# BeerTape_Hardware.net
KiCad netlist of a schematic drawn in EAGLE
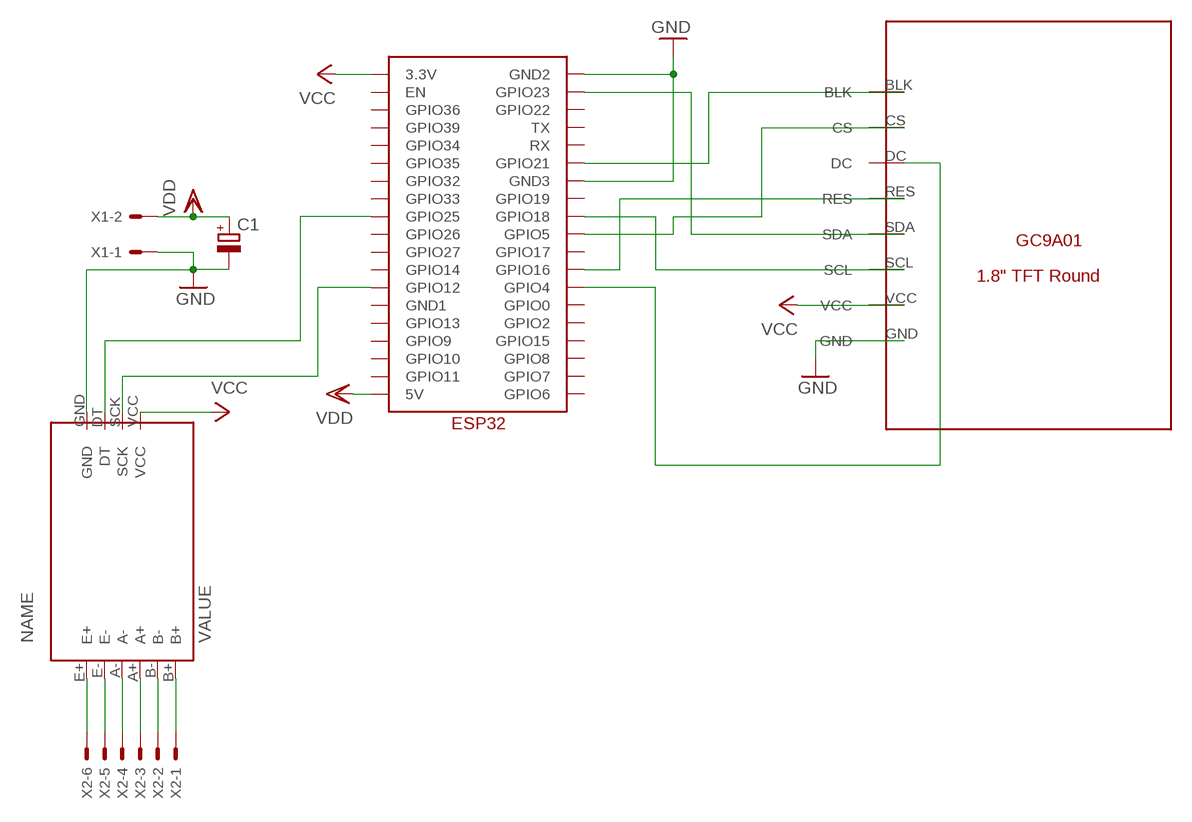
[diagram p0: schematic, sheet 1]

(export (version "E")
  (design (tool "Eeschema 10.0.6"))
  (components
    (comp (ref "C1")
      (value "CPOL-EUE2,5-6E")
      (footprint "eagle-import:E2,5-6E")
      (libsource (lib "eagle-import") (part "CPOL-EUE2,5-6E"))
    )
    (comp (ref "HX711")
      (value "HX711")
      (footprint "eagle-import:HX711")
      (libsource (lib "eagle-import") (part "HX711A"))
    )
    (comp (ref "U$1")
      (value "GC9A01")
      (footprint "eagle-import:GC9A01")
      (libsource (lib "eagle-import") (part "GC9A01"))
    )
    (comp (ref "U$2")
      (value "ESP32")
      (footprint "eagle-import:ESP32")
      (libsource (lib "eagle-import") (part "ESP32"))
    )
    (comp (ref "X1")
      (value "KK-156-2")
      (footprint "eagle-import:KK-156-2")
      (fields (field (name "MF") "MOLEX"))
      (libsource (lib "eagle-import") (part "KK-156-2"))
    )
    (comp (ref "X2")
      (value "22-23-2061")
      (footprint "eagle-import:22-23-2061")
      (fields (field (name "MF") "MOLEX"))
      (libsource (lib "eagle-import") (part "22-23-2061"))
    )
  )
  (nets
    (net (code "1") (name "GND") (class "Default")
      (node (ref "C1") (pin "-") (pinfunction "-_-") (pintype "passive"))
      (node (ref "HX711") (pin "GND") (pinfunction "GND_GND") (pintype "bidirectional"))
      (node (ref "U$1") (pin "GND") (pinfunction "GND_GND") (pintype "bidirectional"))
      (node (ref "U$2") (pin "GND2") (pinfunction "GND2_GND2") (pintype "bidirectional"))
      (node (ref "U$2") (pin "GND3") (pinfunction "GND3_GND3") (pintype "bidirectional"))
      (node (ref "X1") (pin "1") (pinfunction "S_1") (pintype "passive"))
    )
    (net (code "2") (name "Net-(HX711-PadDT)") (class "Default")
      (node (ref "HX711") (pin "DT") (pinfunction "DT_DT") (pintype "bidirectional"))
      (node (ref "U$2") (pin "GPIO25") (pinfunction "GPIO25_GPIO25") (pintype "bidirectional"))
    )
    (net (code "3") (name "Net-(HX711-PadSCK)") (class "Default")
      (node (ref "HX711") (pin "SCK") (pinfunction "SCK_SCK") (pintype "bidirectional"))
      (node (ref "U$2") (pin "GPIO12") (pinfunction "GPIO12_GPIO12") (pintype "bidirectional"))
    )
    (net (code "4") (name "Net-(U$1-PadBLK)") (class "Default")
      (node (ref "U$1") (pin "BLK") (pinfunction "BLK_BLK") (pintype "bidirectional"))
      (node (ref "U$2") (pin "GPIO21") (pinfunction "GPIO21_GPIO21") (pintype "bidirectional"))
    )
    (net (code "5") (name "Net-(U$1-PadCS)") (class "Default")
      (node (ref "U$1") (pin "CS") (pinfunction "CS_CS") (pintype "bidirectional"))
      (node (ref "U$2") (pin "GPIO5") (pinfunction "GPIO5_GPIO5") (pintype "bidirectional"))
    )
    (net (code "6") (name "Net-(U$1-PadDC)") (class "Default")
      (node (ref "U$1") (pin "DC") (pinfunction "DC_DC") (pintype "bidirectional"))
      (node (ref "U$2") (pin "GPIO4") (pinfunction "GPIO4_GPIO4") (pintype "bidirectional"))
    )
    (net (code "7") (name "Net-(U$1-PadRES)") (class "Default")
      (node (ref "U$1") (pin "RES") (pinfunction "RES_RES") (pintype "bidirectional"))
      (node (ref "U$2") (pin "GPIO16") (pinfunction "GPIO16_GPIO16") (pintype "bidirectional"))
    )
    (net (code "8") (name "Net-(U$1-PadSCL)") (class "Default")
      (node (ref "U$1") (pin "SCL") (pinfunction "SCL_SCL") (pintype "bidirectional"))
      (node (ref "U$2") (pin "GPIO18") (pinfunction "GPIO18_GPIO18") (pintype "bidirectional"))
    )
    (net (code "9") (name "Net-(U$1-PadSDA)") (class "Default")
      (node (ref "U$1") (pin "SDA") (pinfunction "SDA_SDA") (pintype "bidirectional"))
      (node (ref "U$2") (pin "GPIO23") (pinfunction "GPIO23_GPIO23") (pintype "bidirectional"))
    )
    (net (code "10") (name "Net-(X2A-S)") (class "Default")
      (node (ref "HX711") (pin "B+") (pinfunction "B+_B+") (pintype "bidirectional"))
      (node (ref "X2") (pin "1") (pinfunction "S_1") (pintype "passive"))
    )
    (net (code "11") (name "Net-(X2B-S)") (class "Default")
      (node (ref "HX711") (pin "B-") (pinfunction "B-_B-") (pintype "bidirectional"))
      (node (ref "X2") (pin "2") (pinfunction "S_2") (pintype "passive"))
    )
    (net (code "12") (name "Net-(X2C-S)") (class "Default")
      (node (ref "HX711") (pin "A+") (pinfunction "A+_A+") (pintype "bidirectional"))
      (node (ref "X2") (pin "3") (pinfunction "S_3") (pintype "passive"))
    )
    (net (code "13") (name "Net-(X2D-S)") (class "Default")
      (node (ref "HX711") (pin "A-") (pinfunction "A-_A-") (pintype "bidirectional"))
      (node (ref "X2") (pin "4") (pinfunction "S_4") (pintype "passive"))
    )
    (net (code "14") (name "Net-(X2E-S)") (class "Default")
      (node (ref "HX711") (pin "E-") (pinfunction "E-_E-") (pintype "bidirectional"))
      (node (ref "X2") (pin "5") (pinfunction "S_5") (pintype "passive"))
    )
    (net (code "15") (name "Net-(X2F-S)") (class "Default")
      (node (ref "HX711") (pin "E+") (pinfunction "E+_E+") (pintype "bidirectional"))
      (node (ref "X2") (pin "6") (pinfunction "S_6") (pintype "passive"))
    )
    (net (code "16") (name "VCC") (class "Default")
      (node (ref "HX711") (pin "VCC") (pinfunction "VCC_VCC") (pintype "bidirectional"))
      (node (ref "U$1") (pin "VCC") (pinfunction "VCC_VCC") (pintype "bidirectional"))
      (node (ref "U$2") (pin "3.3V") (pinfunction "3.3V_3.3V") (pintype "bidirectional"))
    )
    (net (code "17") (name "VDD") (class "Default")
      (node (ref "C1") (pin "+") (pinfunction "+_+") (pintype "passive"))
      (node (ref "U$2") (pin "5V") (pinfunction "5V_5V") (pintype "bidirectional"))
      (node (ref "X1") (pin "2") (pinfunction "S_2") (pintype "passive"))
    )
    (net (code "18") (name "unconnected-(U$2-PadEN)") (class "Default")
      (node (ref "U$2") (pin "EN") (pinfunction "EN_EN") (pintype "bidirectional"))
    )
    (net (code "19") (name "unconnected-(U$2-PadGND1)") (class "Default")
      (node (ref "U$2") (pin "GND1") (pinfunction "GND1_GND1") (pintype "bidirectional"))
    )
    (net (code "20") (name "unconnected-(U$2-PadGPIO0)") (class "Default")
      (node (ref "U$2") (pin "GPIO0") (pinfunction "GPIO0_GPIO0") (pintype "bidirectional"))
    )
    (net (code "21") (name "unconnected-(U$2-PadGPIO2)") (class "Default")
      (node (ref "U$2") (pin "GPIO2") (pinfunction "GPIO2_GPIO2") (pintype "bidirectional"))
    )
    (net (code "22") (name "unconnected-(U$2-PadGPIO6)") (class "Default")
      (node (ref "U$2") (pin "GPIO6") (pinfunction "GPIO6_GPIO6") (pintype "bidirectional"))
    )
    (net (code "23") (name "unconnected-(U$2-PadGPIO7)") (class "Default")
      (node (ref "U$2") (pin "GPIO7") (pinfunction "GPIO7_GPIO7") (pintype "bidirectional"))
    )
    (net (code "24") (name "unconnected-(U$2-PadGPIO8)") (class "Default")
      (node (ref "U$2") (pin "GPIO8") (pinfunction "GPIO8_GPIO8") (pintype "bidirectional"))
    )
    (net (code "25") (name "unconnected-(U$2-PadGPIO9)") (class "Default")
      (node (ref "U$2") (pin "GPIO9") (pinfunction "GPIO9_GPIO9") (pintype "bidirectional"))
    )
    (net (code "26") (name "unconnected-(U$2-PadGPIO10)") (class "Default")
      (node (ref "U$2") (pin "GPIO10") (pinfunction "GPIO10_GPIO10") (pintype "bidirectional"))
    )
    (net (code "27") (name "unconnected-(U$2-PadGPIO11)") (class "Default")
      (node (ref "U$2") (pin "GPIO11") (pinfunction "GPIO11_GPIO11") (pintype "bidirectional"))
    )
    (net (code "28") (name "unconnected-(U$2-PadGPIO13)") (class "Default")
      (node (ref "U$2") (pin "GPIO13") (pinfunction "GPIO13_GPIO13") (pintype "bidirectional"))
    )
    (net (code "29") (name "unconnected-(U$2-PadGPIO14)") (class "Default")
      (node (ref "U$2") (pin "GPIO14") (pinfunction "GPIO14_GPIO14") (pintype "bidirectional"))
    )
    (net (code "30") (name "unconnected-(U$2-PadGPIO15)") (class "Default")
      (node (ref "U$2") (pin "GPIO15") (pinfunction "GPIO15_GPIO15") (pintype "bidirectional"))
    )
    (net (code "31") (name "unconnected-(U$2-PadGPIO17)") (class "Default")
      (node (ref "U$2") (pin "GPIO17") (pinfunction "GPIO17_GPIO17") (pintype "bidirectional"))
    )
    (net (code "32") (name "unconnected-(U$2-PadGPIO19)") (class "Default")
      (node (ref "U$2") (pin "GPIO19") (pinfunction "GPIO19_GPIO19") (pintype "bidirectional"))
    )
    (net (code "33") (name "unconnected-(U$2-PadGPIO22)") (class "Default")
      (node (ref "U$2") (pin "GPIO22") (pinfunction "GPIO22_GPIO22") (pintype "bidirectional"))
    )
    (net (code "34") (name "unconnected-(U$2-PadGPIO26)") (class "Default")
      (node (ref "U$2") (pin "GPIO26") (pinfunction "GPIO26_GPIO26") (pintype "bidirectional"))
    )
    (net (code "35") (name "unconnected-(U$2-PadGPIO27)") (class "Default")
      (node (ref "U$2") (pin "GPIO27") (pinfunction "GPIO27_GPIO27") (pintype "bidirectional"))
    )
    (net (code "36") (name "unconnected-(U$2-PadGPIO32)") (class "Default")
      (node (ref "U$2") (pin "GPIO32") (pinfunction "GPIO32_GPIO32") (pintype "bidirectional"))
    )
    (net (code "37") (name "unconnected-(U$2-PadGPIO33)") (class "Default")
      (node (ref "U$2") (pin "GPIO33") (pinfunction "GPIO33_GPIO33") (pintype "bidirectional"))
    )
    (net (code "38") (name "unconnected-(U$2-PadGPIO34)") (class "Default")
      (node (ref "U$2") (pin "GPIO34") (pinfunction "GPIO34_GPIO34") (pintype "bidirectional"))
    )
    (net (code "39") (name "unconnected-(U$2-PadGPIO35)") (class "Default")
      (node (ref "U$2") (pin "GPIO35") (pinfunction "GPIO35_GPIO35") (pintype "bidirectional"))
    )
    (net (code "40") (name "unconnected-(U$2-PadGPIO36)") (class "Default")
      (node (ref "U$2") (pin "GPIO36") (pinfunction "GPIO36_GPIO36") (pintype "bidirectional"))
    )
    (net (code "41") (name "unconnected-(U$2-PadGPIO39)") (class "Default")
      (node (ref "U$2") (pin "GPIO39") (pinfunction "GPIO39_GPIO39") (pintype "bidirectional"))
    )
    (net (code "42") (name "unconnected-(U$2-PadRX)") (class "Default")
      (node (ref "U$2") (pin "RX") (pinfunction "RX_RX") (pintype "bidirectional"))
    )
    (net (code "43") (name "unconnected-(U$2-PadTX)") (class "Default")
      (node (ref "U$2") (pin "TX") (pinfunction "TX_TX") (pintype "bidirectional"))
    )
  )
)
